# rgb-led-cc-driver-mk-1_0.net
KiCad netlist of a schematic drawn in EAGLE
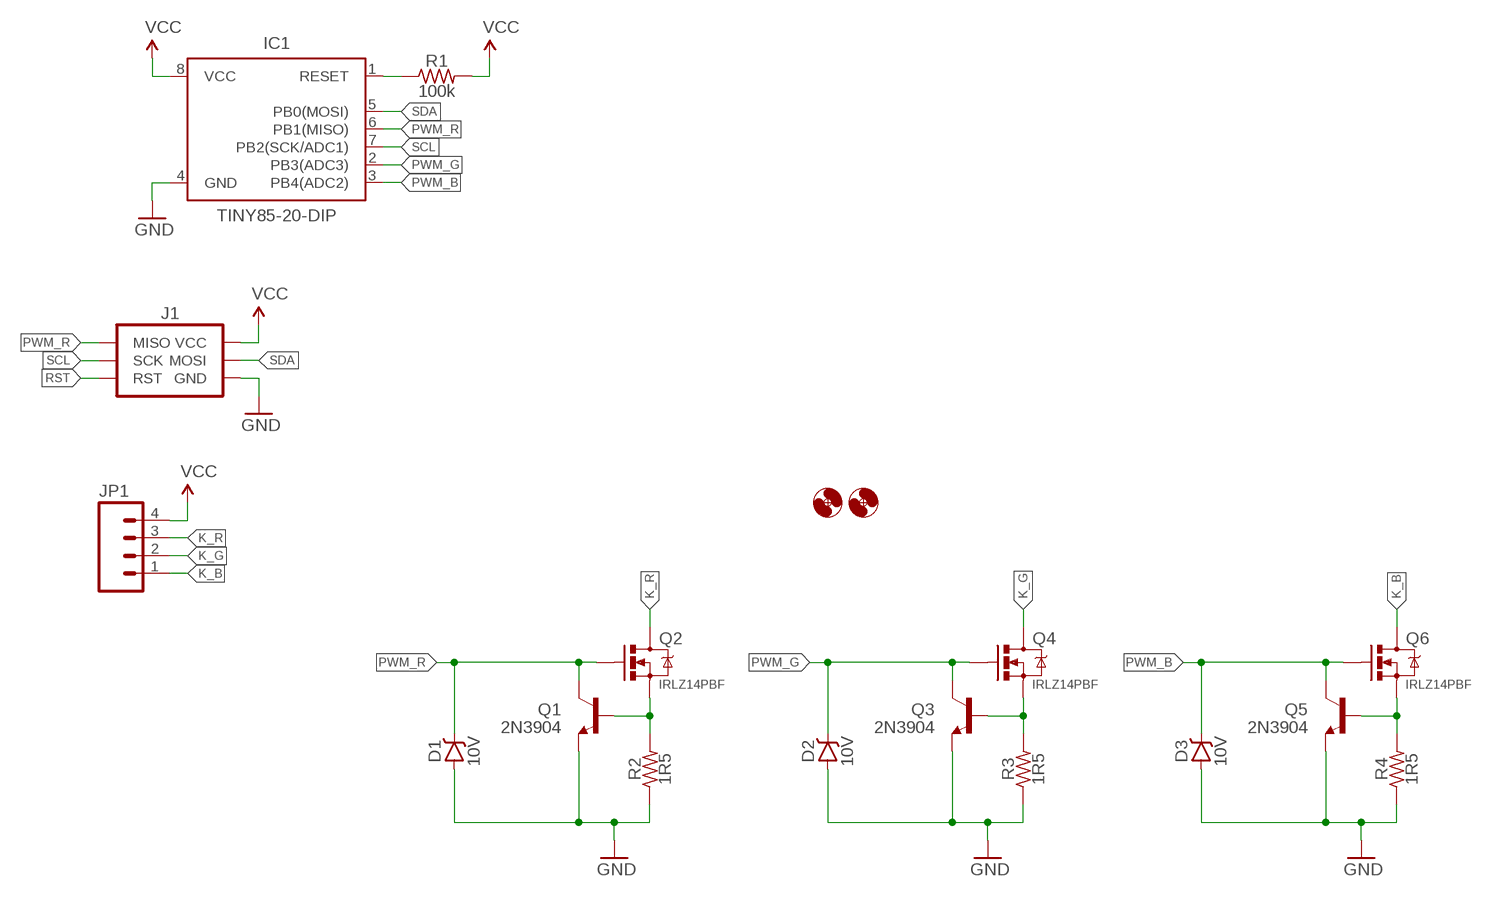
[diagram p0: schematic, sheet 1]

(export (version "E")
  (design (tool "Eeschema 10.0.6"))
  (components
    (comp (ref "D1")
      (value "10V")
      (footprint "eagle-import:DIODE-7.62MM")
      (libsource (lib "eagle-import") (part "DIODE-ZENERPTH-7.62MM"))
    )
    (comp (ref "D2")
      (value "10V")
      (footprint "eagle-import:DIODE-7.62MM")
      (libsource (lib "eagle-import") (part "DIODE-ZENERPTH-7.62MM"))
    )
    (comp (ref "D3")
      (value "10V")
      (footprint "eagle-import:DIODE-7.62MM")
      (libsource (lib "eagle-import") (part "DIODE-ZENERPTH-7.62MM"))
    )
    (comp (ref "H1")
      (value "HOLE#2")
      (footprint "eagle-import:HOLE-#2")
      (libsource (lib "eagle-import") (part "HOLE#2"))
    )
    (comp (ref "H2")
      (value "HOLE#2")
      (footprint "eagle-import:HOLE-#2")
      (libsource (lib "eagle-import") (part "HOLE#2"))
    )
    (comp (ref "IC1")
      (value "TINY85-20-DIP")
      (footprint "eagle-import:DIP08")
      (libsource (lib "eagle-import") (part "ATTINY45TINY85-20-DIP"))
    )
    (comp (ref "J1")
      (value "AVR_SPI_PRG_6PTH_INLINE_I2C")
      (footprint "eagle-import:AVR_ISP_INLINE_PTH_I2C")
      (libsource (lib "eagle-import") (part "AVR_SPI_PRG_6PTH_INLINE_I2C"))
    )
    (comp (ref "JP1")
      (value "M04PTH")
      (footprint "eagle-import:1X04-PTH-VERT")
      (libsource (lib "eagle-import") (part "M04PTH"))
    )
    (comp (ref "Q1")
      (value "2N3904")
      (footprint "eagle-import:TO-92-AMMO")
      (libsource (lib "eagle-import") (part "TRANSISTOR_NPNTO-92-AMMO-EBC"))
    )
    (comp (ref "Q2")
      (value "IRLZ14PBF")
      (footprint "eagle-import:TO220-THERMPAD")
      (libsource (lib "eagle-import") (part "MOSFET-NCHANNELTO-220"))
    )
    (comp (ref "Q3")
      (value "2N3904")
      (footprint "eagle-import:TO-92-AMMO")
      (libsource (lib "eagle-import") (part "TRANSISTOR_NPNTO-92-AMMO-EBC"))
    )
    (comp (ref "Q4")
      (value "IRLZ14PBF")
      (footprint "eagle-import:TO220-THERMPAD")
      (libsource (lib "eagle-import") (part "MOSFET-NCHANNELTO-220"))
    )
    (comp (ref "Q5")
      (value "2N3904")
      (footprint "eagle-import:TO-92-AMMO")
      (libsource (lib "eagle-import") (part "TRANSISTOR_NPNTO-92-AMMO-EBC"))
    )
    (comp (ref "Q6")
      (value "IRLZ14PBF")
      (footprint "eagle-import:TO220-THERMPAD")
      (libsource (lib "eagle-import") (part "MOSFET-NCHANNELTO-220"))
    )
    (comp (ref "R1")
      (value "100k")
      (footprint "eagle-import:RESISTOR-AXIAL-PTH-6.35MM")
      (libsource (lib "eagle-import") (part "RESISTORPTH-AXIAL-6.35MM"))
    )
    (comp (ref "R2")
      (value "1R5")
      (footprint "eagle-import:RESISTOR-AXIAL-PTH-10.16MM")
      (libsource (lib "eagle-import") (part "RESISTORPTH-AXIAL-10.16MM"))
    )
    (comp (ref "R3")
      (value "1R5")
      (footprint "eagle-import:RESISTOR-AXIAL-PTH-10.16MM")
      (libsource (lib "eagle-import") (part "RESISTORPTH-AXIAL-10.16MM"))
    )
    (comp (ref "R4")
      (value "1R5")
      (footprint "eagle-import:RESISTOR-AXIAL-PTH-10.16MM")
      (libsource (lib "eagle-import") (part "RESISTORPTH-AXIAL-10.16MM"))
    )
  )
  (nets
    (net (code "1") (name "GND") (class "Default")
      (node (ref "D1") (pin "A") (pinfunction "A_A") (pintype "passive"))
      (node (ref "D2") (pin "A") (pinfunction "A_A") (pintype "passive"))
      (node (ref "D3") (pin "A") (pinfunction "A_A") (pintype "passive"))
      (node (ref "IC1") (pin "4") (pinfunction "GND_4") (pintype "bidirectional"))
      (node (ref "J1") (pin "GND") (pinfunction "GND_GND") (pintype "passive"))
      (node (ref "Q1") (pin "1") (pinfunction "E_1") (pintype "passive"))
      (node (ref "Q3") (pin "1") (pinfunction "E_1") (pintype "passive"))
      (node (ref "Q5") (pin "1") (pinfunction "E_1") (pintype "passive"))
      (node (ref "R2") (pin "P$1") (pinfunction "1_P$1") (pintype "passive"))
      (node (ref "R3") (pin "P$1") (pinfunction "1_P$1") (pintype "passive"))
      (node (ref "R4") (pin "P$1") (pinfunction "1_P$1") (pintype "passive"))
    )
    (net (code "2") (name "K_B") (class "Default")
      (node (ref "JP1") (pin "1") (pinfunction "1_1") (pintype "passive"))
      (node (ref "Q6") (pin "2@1") (pinfunction "D_2@1") (pintype "passive"))
      (node (ref "Q6") (pin "2@2") (pinfunction "D_2@2") (pintype "passive"))
    )
    (net (code "3") (name "K_G") (class "Default")
      (node (ref "JP1") (pin "2") (pinfunction "2_2") (pintype "passive"))
      (node (ref "Q4") (pin "2@1") (pinfunction "D_2@1") (pintype "passive"))
      (node (ref "Q4") (pin "2@2") (pinfunction "D_2@2") (pintype "passive"))
    )
    (net (code "4") (name "K_R") (class "Default")
      (node (ref "JP1") (pin "3") (pinfunction "3_3") (pintype "passive"))
      (node (ref "Q2") (pin "2@1") (pinfunction "D_2@1") (pintype "passive"))
      (node (ref "Q2") (pin "2@2") (pinfunction "D_2@2") (pintype "passive"))
    )
    (net (code "5") (name "Net-(Q1-B)") (class "Default")
      (node (ref "Q1") (pin "2") (pinfunction "B_2") (pintype "passive"))
      (node (ref "Q2") (pin "3") (pinfunction "S_3") (pintype "passive"))
      (node (ref "R2") (pin "P$2") (pinfunction "2_P$2") (pintype "passive"))
    )
    (net (code "6") (name "Net-(Q3-B)") (class "Default")
      (node (ref "Q3") (pin "2") (pinfunction "B_2") (pintype "passive"))
      (node (ref "Q4") (pin "3") (pinfunction "S_3") (pintype "passive"))
      (node (ref "R3") (pin "P$2") (pinfunction "2_P$2") (pintype "passive"))
    )
    (net (code "7") (name "Net-(Q5-B)") (class "Default")
      (node (ref "Q5") (pin "2") (pinfunction "B_2") (pintype "passive"))
      (node (ref "Q6") (pin "3") (pinfunction "S_3") (pintype "passive"))
      (node (ref "R4") (pin "P$2") (pinfunction "2_P$2") (pintype "passive"))
    )
    (net (code "8") (name "PWM_B") (class "Default")
      (node (ref "D3") (pin "K") (pinfunction "C_K") (pintype "passive"))
      (node (ref "IC1") (pin "3") (pinfunction "PB4(ADC2)_3") (pintype "bidirectional"))
      (node (ref "Q5") (pin "3") (pinfunction "C_3") (pintype "passive"))
      (node (ref "Q6") (pin "1") (pinfunction "G_1") (pintype "passive"))
    )
    (net (code "9") (name "PWM_G") (class "Default")
      (node (ref "D2") (pin "K") (pinfunction "C_K") (pintype "passive"))
      (node (ref "IC1") (pin "2") (pinfunction "PB3(ADC3)_2") (pintype "bidirectional"))
      (node (ref "Q3") (pin "3") (pinfunction "C_3") (pintype "passive"))
      (node (ref "Q4") (pin "1") (pinfunction "G_1") (pintype "passive"))
    )
    (net (code "10") (name "PWM_R") (class "Default")
      (node (ref "D1") (pin "K") (pinfunction "C_K") (pintype "passive"))
      (node (ref "IC1") (pin "6") (pinfunction "PB1(MISO)_6") (pintype "bidirectional"))
      (node (ref "J1") (pin "MISO") (pinfunction "MISO_MISO") (pintype "passive"))
      (node (ref "Q1") (pin "3") (pinfunction "C_3") (pintype "passive"))
      (node (ref "Q2") (pin "1") (pinfunction "G_1") (pintype "passive"))
    )
    (net (code "11") (name "RST") (class "Default")
      (node (ref "IC1") (pin "1") (pinfunction "RESET_1") (pintype "bidirectional"))
      (node (ref "J1") (pin "RESET") (pinfunction "RST_RESET") (pintype "passive"))
      (node (ref "R1") (pin "P$1") (pinfunction "1_P$1") (pintype "passive"))
    )
    (net (code "12") (name "SCL") (class "Default")
      (node (ref "IC1") (pin "7") (pinfunction "PB2(SCK/ADC1)_7") (pintype "bidirectional"))
      (node (ref "J1") (pin "SCK") (pinfunction "SCK_SCK") (pintype "passive"))
    )
    (net (code "13") (name "SDA") (class "Default")
      (node (ref "IC1") (pin "5") (pinfunction "PB0(MOSI)_5") (pintype "bidirectional"))
      (node (ref "J1") (pin "MOSI") (pinfunction "MOSI_MOSI") (pintype "passive"))
    )
    (net (code "14") (name "VCC") (class "Default")
      (node (ref "IC1") (pin "8") (pinfunction "VCC_8") (pintype "bidirectional"))
      (node (ref "J1") (pin "VCC") (pinfunction "VCC_VCC") (pintype "passive"))
      (node (ref "JP1") (pin "4") (pinfunction "4_4") (pintype "passive"))
      (node (ref "R1") (pin "P$2") (pinfunction "2_P$2") (pintype "passive"))
    )
  )
)
